# OBI_SlaveBoard_rev4.net
KiCad netlist of a schematic drawn in EAGLE
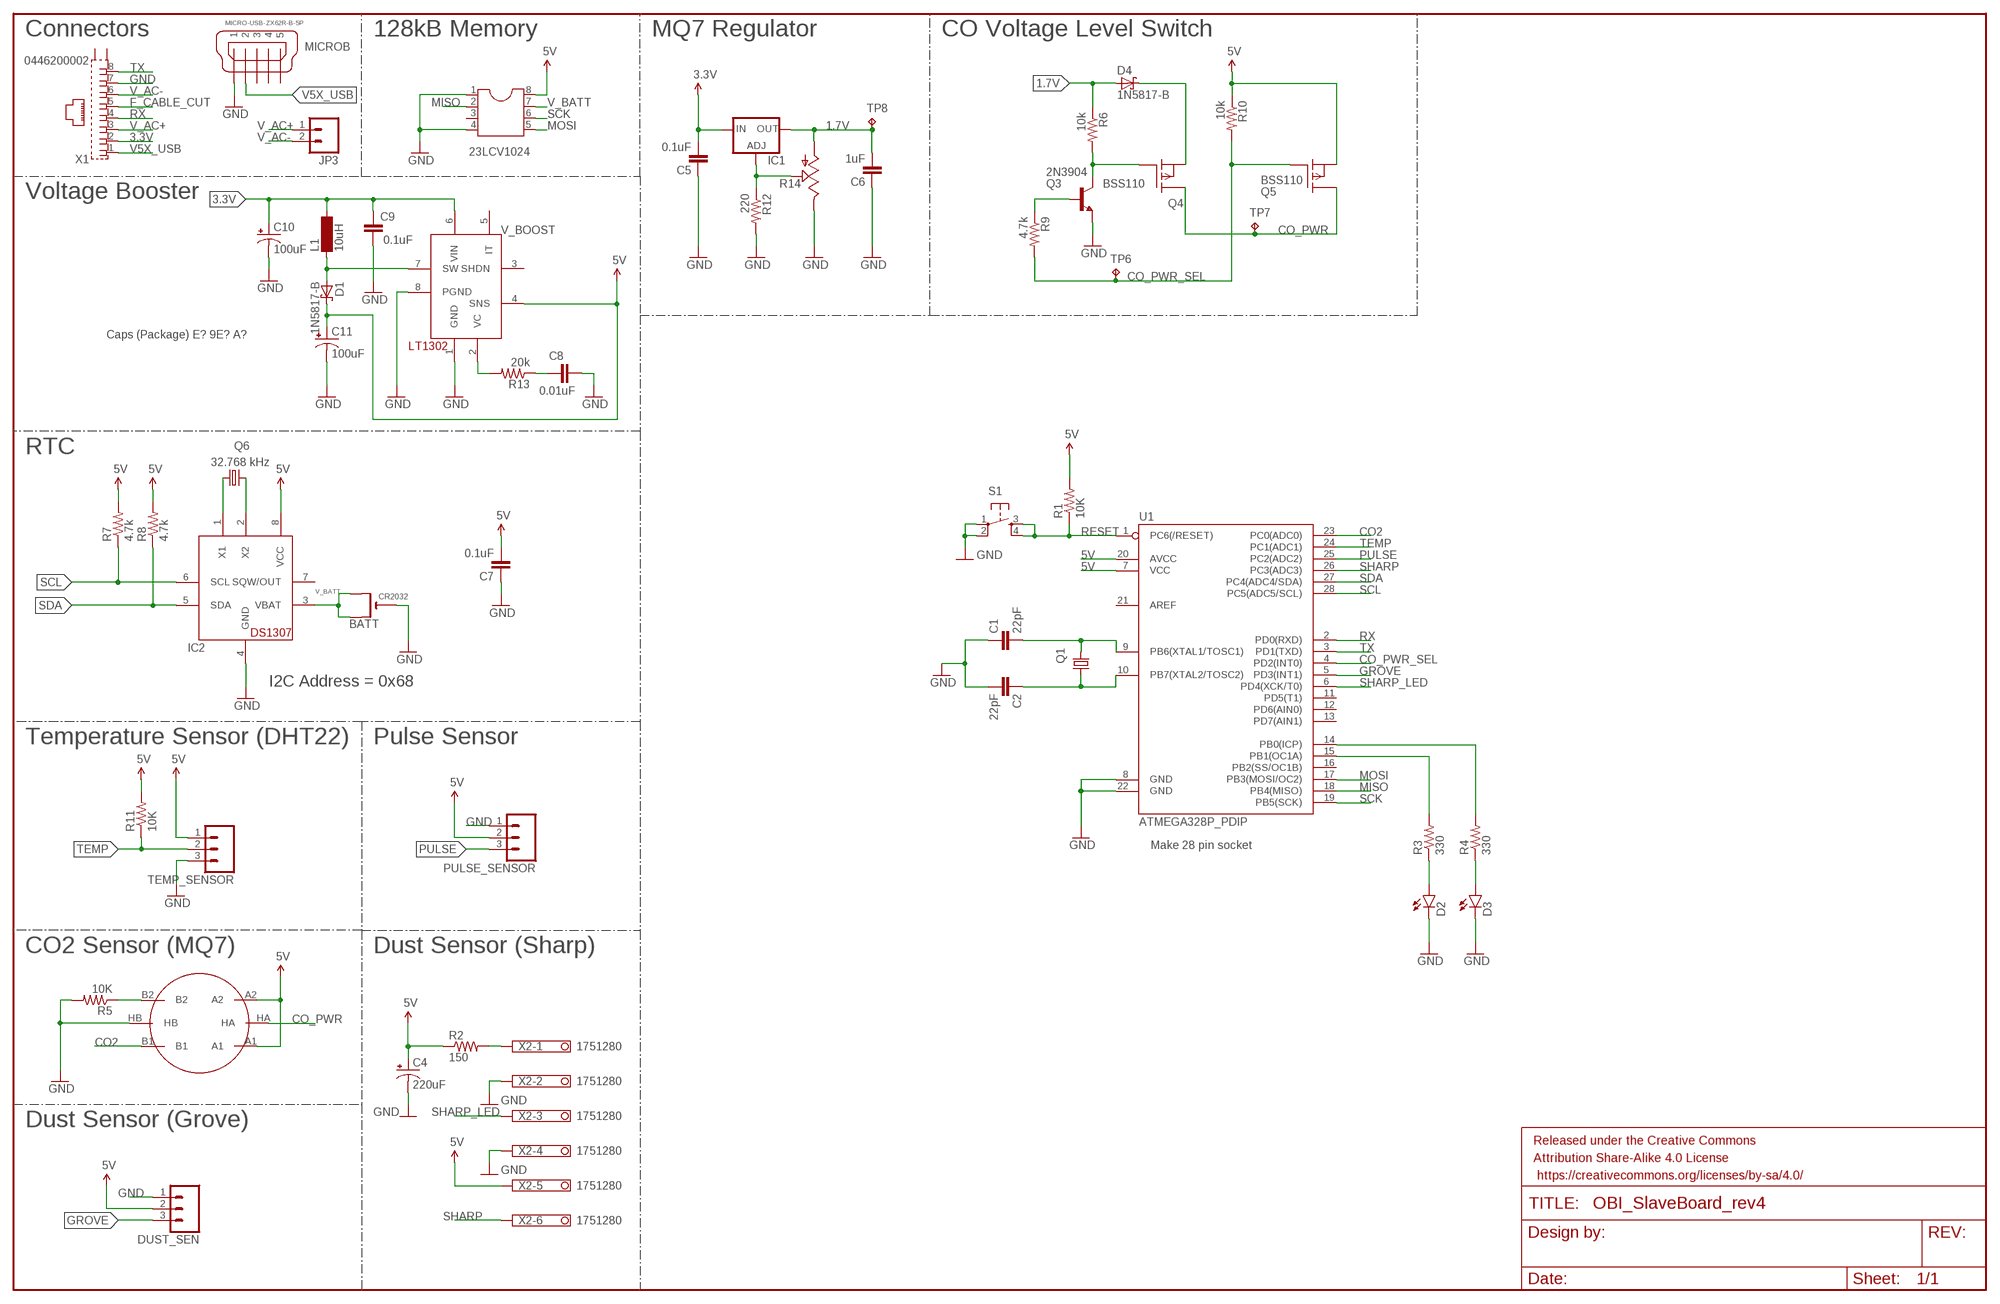
[diagram p0: schematic, sheet 1]

(export (version "E")
  (design (tool "Eeschema 10.0.6"))
  (components
    (comp (ref "23LCV1024")
      (value "DIL8S")
      (footprint "eagle-import:SOCKET-08")
      (libsource (lib "eagle-import") (part "DIL8S"))
    )
    (comp (ref "BATT")
      (value "CR2032THM")
      (footprint "eagle-import:CR2032-THRU")
      (libsource (lib "eagle-import") (part "CR2032THM"))
    )
    (comp (ref "C1")
      (value "22pF")
      (footprint "eagle-import:CAP-PTH-SMALL-KIT")
      (libsource (lib "eagle-import") (part "CAPKIT"))
    )
    (comp (ref "C2")
      (value "22pF")
      (footprint "eagle-import:CAP-PTH-SMALL-KIT")
      (libsource (lib "eagle-import") (part "CAPKIT"))
    )
    (comp (ref "C4")
      (value "220uF")
      (footprint "eagle-import:CPOL-RADIAL-10UF-25V")
      (libsource (lib "eagle-import") (part "CAP_POLPTH2"))
    )
    (comp (ref "C5")
      (value "0.1uF")
      (footprint "eagle-import:CAP-PTH-SMALL-KIT")
      (libsource (lib "eagle-import") (part "CAPKIT"))
    )
    (comp (ref "C6")
      (value "1uF")
      (footprint "eagle-import:CAP-PTH-SMALL-KIT")
      (libsource (lib "eagle-import") (part "CAPKIT"))
    )
    (comp (ref "C7")
      (value "0.1uF")
      (footprint "eagle-import:CAP-PTH-SMALL-KIT")
      (libsource (lib "eagle-import") (part "CAPKIT"))
    )
    (comp (ref "C8")
      (value "0.01uF")
      (footprint "eagle-import:CAP-PTH-SMALL-KIT")
      (libsource (lib "eagle-import") (part "CAPKIT"))
    )
    (comp (ref "C9")
      (value "0.1uF")
      (footprint "eagle-import:CAP-PTH-SMALL-KIT")
      (libsource (lib "eagle-import") (part "CAPKIT"))
    )
    (comp (ref "C10")
      (value "100uF")
      (footprint "eagle-import:TT2D5")
      (libsource (lib "eagle-import") (part "CPOL-USTT2D5"))
    )
    (comp (ref "C11")
      (value "100uF")
      (footprint "eagle-import:TT2D5")
      (libsource (lib "eagle-import") (part "CPOL-USTT2D5"))
    )
    (comp (ref "CO2_SENSOR")
      (value "METHANE_SENSOR")
      (footprint "eagle-import:MQ-3")
      (libsource (lib "eagle-import") (part "METHANE_SENSOR"))
    )
    (comp (ref "D1")
      (value "1N5817-B")
      (footprint "eagle-import:DO41-10")
      (libsource (lib "eagle-import") (part "SCHOTTKY-DIODEDO41"))
    )
    (comp (ref "D2")
      (value "LED5MM")
      (footprint "eagle-import:LED5MM")
      (libsource (lib "eagle-import") (part "LED5MM"))
    )
    (comp (ref "D3")
      (value "LED5MM")
      (footprint "eagle-import:LED5MM")
      (libsource (lib "eagle-import") (part "LED5MM"))
    )
    (comp (ref "D4")
      (value "1N5817-B")
      (footprint "eagle-import:DO41-10")
      (libsource (lib "eagle-import") (part "SCHOTTKY-DIODEDO41"))
    )
    (comp (ref "DUST_SEN")
      (value "M03SCREW")
      (footprint "eagle-import:SCREWTERMINAL-3.5MM-3")
      (libsource (lib "eagle-import") (part "M03SCREW"))
    )
    (comp (ref "FRAME1")
      (value "FRAME-LEDGER")
      (footprint "eagle-import:CREATIVE_COMMONS")
      (libsource (lib "eagle-import") (part "FRAME-LEDGER"))
    )
    (comp (ref "IC1")
      (value "LM317TS")
      (footprint "eagle-import:317TS")
      (libsource (lib "eagle-import") (part "LM317TS"))
    )
    (comp (ref "IC2")
      (value "DS1307")
      (footprint "eagle-import:DIL08")
      (libsource (lib "eagle-import") (part "DS1307"))
    )
    (comp (ref "JP3")
      (value "M023.5MM")
      (footprint "eagle-import:SCREWTERMINAL-3.5MM-2")
      (libsource (lib "eagle-import") (part "M023.5MM"))
    )
    (comp (ref "L1")
      (value "10uH")
      (footprint "eagle-import:BS11")
      (libsource (lib "eagle-import") (part "BS11"))
    )
    (comp (ref "MICROB")
      (value "MICRO-USB-ZX62R-B-5P")
      (footprint "eagle-import:ZX62R-B-5P")
      (libsource (lib "eagle-import") (part "MICRO-USB-ZX62R-B-5P"))
    )
    (comp (ref "PULSE_SENSOR")
      (value "M03SCREW")
      (footprint "eagle-import:SCREWTERMINAL-3.5MM-3")
      (libsource (lib "eagle-import") (part "M03SCREW"))
    )
    (comp (ref "Q1")
      (value "CRYSTALHC49S")
      (footprint "eagle-import:HC49_S")
      (libsource (lib "eagle-import") (part "CRYSTALHC49S"))
    )
    (comp (ref "Q3")
      (value "2N3904")
      (footprint "eagle-import:TO-92")
      (libsource (lib "eagle-import") (part "TRANSISTOR_NPN2N3904"))
    )
    (comp (ref "Q4")
      (value "BSS110")
      (footprint "eagle-import:TO92")
      (libsource (lib "eagle-import") (part "BSS110"))
    )
    (comp (ref "Q5")
      (value "BSS110")
      (footprint "eagle-import:TO92")
      (libsource (lib "eagle-import") (part "BSS110"))
    )
    (comp (ref "Q6")
      (value "32.768 kHz")
      (footprint "eagle-import:TC26V")
      (libsource (lib "eagle-import") (part "CRYSTALTC26V"))
    )
    (comp (ref "R1")
      (value "10K")
      (footprint "eagle-import:AXIAL-0.4")
      (libsource (lib "eagle-import") (part "RESISTORPTH-1/4W"))
    )
    (comp (ref "R2")
      (value "150")
      (footprint "eagle-import:AXIAL-0.4")
      (libsource (lib "eagle-import") (part "SparkFun-Resistors_RESISTORPTH-1/4W"))
    )
    (comp (ref "R3")
      (value "330")
      (footprint "eagle-import:AXIAL-0.4")
      (libsource (lib "eagle-import") (part "SparkFun-Resistors_RESISTORPTH-1/4W"))
    )
    (comp (ref "R4")
      (value "330")
      (footprint "eagle-import:AXIAL-0.4")
      (libsource (lib "eagle-import") (part "SparkFun-Resistors_RESISTORPTH-1/4W"))
    )
    (comp (ref "R5")
      (value "10K")
      (footprint "eagle-import:AXIAL-0.4")
      (libsource (lib "eagle-import") (part "RESISTORPTH-1/4W"))
    )
    (comp (ref "R6")
      (value "10k")
      (footprint "eagle-import:AXIAL-0.4")
      (libsource (lib "eagle-import") (part "SparkFun-Resistors_RESISTORPTH-1/4W"))
    )
    (comp (ref "R7")
      (value "4.7k")
      (footprint "eagle-import:AXIAL-0.4")
      (libsource (lib "eagle-import") (part "RESISTORPTH-1/4W"))
    )
    (comp (ref "R8")
      (value "4.7k")
      (footprint "eagle-import:AXIAL-0.4")
      (libsource (lib "eagle-import") (part "RESISTORPTH-1/4W"))
    )
    (comp (ref "R9")
      (value "4.7k")
      (footprint "eagle-import:AXIAL-0.4")
      (libsource (lib "eagle-import") (part "SparkFun-Resistors_RESISTORPTH-1/4W"))
    )
    (comp (ref "R10")
      (value "10k")
      (footprint "eagle-import:AXIAL-0.4")
      (libsource (lib "eagle-import") (part "SparkFun-Resistors_RESISTORPTH-1/4W"))
    )
    (comp (ref "R11")
      (value "10K")
      (footprint "eagle-import:AXIAL-0.4")
      (libsource (lib "eagle-import") (part "SparkFun-Resistors_RESISTORPTH-1/4W"))
    )
    (comp (ref "R12")
      (value "220")
      (footprint "eagle-import:AXIAL-0.4")
      (libsource (lib "eagle-import") (part "SparkFun-Resistors_RESISTORPTH-1/4W"))
    )
    (comp (ref "R13")
      (value "20k")
      (footprint "eagle-import:AXIAL-0.4")
      (libsource (lib "eagle-import") (part "SparkFun-Resistors_RESISTORPTH-1/4W"))
    )
    (comp (ref "R14")
      (value "TRIM_US-CT6")
      (footprint "eagle-import:CT6")
      (libsource (lib "eagle-import") (part "TRIM_US-CT6"))
    )
    (comp (ref "S1")
      (value "TAC_SWITCHPTH")
      (footprint "eagle-import:TACTILE-PTH")
      (libsource (lib "eagle-import") (part "TAC_SWITCHPTH"))
    )
    (comp (ref "TEMP_SENSOR")
      (value "M03SCREW")
      (footprint "eagle-import:SCREWTERMINAL-3.5MM-3")
      (libsource (lib "eagle-import") (part "M03SCREW"))
    )
    (comp (ref "TP6")
      (value "TPPAD1-13")
      (footprint "eagle-import:P1-13")
      (libsource (lib "eagle-import") (part "TPPAD1-13"))
    )
    (comp (ref "TP7")
      (value "TPPAD1-13")
      (footprint "eagle-import:P1-13")
      (libsource (lib "eagle-import") (part "TPPAD1-13"))
    )
    (comp (ref "TP8")
      (value "TPPAD1-13")
      (footprint "eagle-import:P1-13")
      (libsource (lib "eagle-import") (part "TPPAD1-13"))
    )
    (comp (ref "U1")
      (value "ATMEGA328P_PDIP")
      (footprint "eagle-import:DIL28-3")
      (libsource (lib "eagle-import") (part "ATMEGA328P_PDIP"))
    )
    (comp (ref "V_BOOST")
      (value "LT1302")
      (footprint "eagle-import:DIL08")
      (libsource (lib "eagle-import") (part "LT1302"))
    )
    (comp (ref "X1")
      (value "0446200002")
      (footprint "eagle-import:0446200002")
      (fields (field (name "MF") "MOLEX"))
      (libsource (lib "eagle-import") (part "0446200002"))
    )
    (comp (ref "X2")
      (value "1751280")
      (footprint "eagle-import:1751280")
      (libsource (lib "eagle-import") (part "1751280"))
    )
  )
  (nets
    (net (code "1") (name "/CO2") (class "Default")
      (node (ref "CO2_SENSOR") (pin "B1") (pinfunction "B1_B1") (pintype "bidirectional"))
      (node (ref "U1") (pin "23") (pinfunction "PC0(ADC0)_23") (pintype "bidirectional"))
    )
    (net (code "2") (name "/CO_PWR") (class "Default")
      (node (ref "CO2_SENSOR") (pin "HA") (pinfunction "HA_HA") (pintype "bidirectional"))
      (node (ref "Q4") (pin "3") (pinfunction "D_3") (pintype "passive"))
      (node (ref "Q5") (pin "3") (pinfunction "D_3") (pintype "passive"))
      (node (ref "TP7") (pin "TP") (pinfunction "TP_TP") (pintype "input"))
    )
    (net (code "3") (name "/CO_PWR_SEL") (class "Default")
      (node (ref "Q5") (pin "2") (pinfunction "G_2") (pintype "passive"))
      (node (ref "R10") (pin "P$2") (pinfunction "2_P$2") (pintype "passive"))
      (node (ref "R9") (pin "P$2") (pinfunction "2_P$2") (pintype "passive"))
      (node (ref "TP6") (pin "TP") (pinfunction "TP_TP") (pintype "input"))
      (node (ref "U1") (pin "4") (pinfunction "PD2(INT0)_4") (pintype "bidirectional"))
    )
    (net (code "4") (name "/F_CABLE_CUT") (class "Default")
      (node (ref "X1") (pin "5") (pinfunction "5_5") (pintype "passive"))
    )
    (net (code "5") (name "/MISO") (class "Default")
      (node (ref "23LCV1024") (pin "2") (pinfunction "2_2") (pintype "passive"))
      (node (ref "U1") (pin "18") (pinfunction "PB4(MISO)_18") (pintype "bidirectional"))
    )
    (net (code "6") (name "/MOSI") (class "Default")
      (node (ref "23LCV1024") (pin "5") (pinfunction "5_5") (pintype "passive"))
      (node (ref "U1") (pin "17") (pinfunction "PB3(MOSI/OC2)_17") (pintype "bidirectional"))
    )
    (net (code "7") (name "/RESET") (class "Default")
      (node (ref "R1") (pin "P$1") (pinfunction "1_P$1") (pintype "passive"))
      (node (ref "S1") (pin "3") (pinfunction "3_3") (pintype "passive"))
      (node (ref "S1") (pin "4") (pinfunction "4_4") (pintype "passive"))
      (node (ref "U1") (pin "1") (pinfunction "PC6(/RESET)_1") (pintype "bidirectional"))
    )
    (net (code "8") (name "/RX") (class "Default")
      (node (ref "U1") (pin "2") (pinfunction "PD0(RXD)_2") (pintype "bidirectional"))
      (node (ref "X1") (pin "4") (pinfunction "4_4") (pintype "passive"))
    )
    (net (code "9") (name "/SCK") (class "Default")
      (node (ref "23LCV1024") (pin "6") (pinfunction "6_6") (pintype "passive"))
      (node (ref "U1") (pin "19") (pinfunction "PB5(SCK)_19") (pintype "bidirectional"))
    )
    (net (code "10") (name "/SHARP") (class "Default")
      (node (ref "U1") (pin "26") (pinfunction "PC3(ADC3)_26") (pintype "bidirectional"))
      (node (ref "X2") (pin "6") (pinfunction "K_6") (pintype "passive"))
    )
    (net (code "11") (name "/SHARP_LED") (class "Default")
      (node (ref "U1") (pin "6") (pinfunction "PD4(XCK/T0)_6") (pintype "bidirectional"))
      (node (ref "X2") (pin "3") (pinfunction "K_3") (pintype "passive"))
    )
    (net (code "12") (name "/TX") (class "Default")
      (node (ref "U1") (pin "3") (pinfunction "PD1(TXD)_3") (pintype "bidirectional"))
      (node (ref "X1") (pin "8") (pinfunction "8_8") (pintype "passive"))
    )
    (net (code "13") (name "/V_AC+") (class "Default")
      (node (ref "JP3") (pin "1") (pinfunction "1_1") (pintype "passive"))
      (node (ref "X1") (pin "3") (pinfunction "3_3") (pintype "passive"))
    )
    (net (code "14") (name "/V_AC-") (class "Default")
      (node (ref "JP3") (pin "2") (pinfunction "2_2") (pintype "passive"))
      (node (ref "X1") (pin "6") (pinfunction "6_6") (pintype "passive"))
    )
    (net (code "15") (name "/V_BATT") (class "Default")
      (node (ref "23LCV1024") (pin "7") (pinfunction "7_7") (pintype "passive"))
      (node (ref "BATT") (pin "+1") (pinfunction "+_+1") (pintype "passive"))
      (node (ref "BATT") (pin "+2") (pinfunction "+1_+2") (pintype "passive"))
      (node (ref "IC2") (pin "3") (pinfunction "VBAT_3") (pintype "power_in"))
    )
    (net (code "16") (name "1.7V") (class "Default")
      (node (ref "C6") (pin "2") (pinfunction "2_2") (pintype "passive"))
      (node (ref "D4") (pin "A") (pinfunction "A_A") (pintype "passive"))
      (node (ref "IC1") (pin "2") (pinfunction "OUT_2") (pintype "passive"))
      (node (ref "R14") (pin "A") (pinfunction "A_A") (pintype "passive"))
      (node (ref "R6") (pin "P$1") (pinfunction "1_P$1") (pintype "passive"))
      (node (ref "TP8") (pin "TP") (pinfunction "TP_TP") (pintype "input"))
    )
    (net (code "17") (name "3.3V") (class "Default")
      (node (ref "C10") (pin "+") (pinfunction "+_+") (pintype "passive"))
      (node (ref "C5") (pin "2") (pinfunction "2_2") (pintype "passive"))
      (node (ref "C9") (pin "1") (pinfunction "1_1") (pintype "passive"))
      (node (ref "IC1") (pin "3") (pinfunction "IN_3") (pintype "input"))
      (node (ref "L1") (pin "2") (pinfunction "2_2") (pintype "passive"))
      (node (ref "V_BOOST") (pin "6") (pinfunction "VIN_6") (pintype "input"))
      (node (ref "X1") (pin "2") (pinfunction "2_2") (pintype "passive"))
    )
    (net (code "18") (name "5V") (class "Default")
      (node (ref "23LCV1024") (pin "8") (pinfunction "8_8") (pintype "passive"))
      (node (ref "C11") (pin "+") (pinfunction "+_+") (pintype "passive"))
      (node (ref "C4") (pin "1") (pinfunction "+_1") (pintype "passive"))
      (node (ref "C7") (pin "2") (pinfunction "2_2") (pintype "passive"))
      (node (ref "CO2_SENSOR") (pin "A1") (pinfunction "A1_A1") (pintype "bidirectional"))
      (node (ref "CO2_SENSOR") (pin "A2") (pinfunction "A2_A2") (pintype "bidirectional"))
      (node (ref "D1") (pin "C") (pinfunction "C_C") (pintype "passive"))
      (node (ref "DUST_SEN") (pin "2") (pinfunction "2_2") (pintype "passive"))
      (node (ref "IC2") (pin "8") (pinfunction "VCC_8") (pintype "power_in"))
      (node (ref "PULSE_SENSOR") (pin "2") (pinfunction "2_2") (pintype "passive"))
      (node (ref "Q5") (pin "1") (pinfunction "S_1") (pintype "passive"))
      (node (ref "R1") (pin "P$2") (pinfunction "2_P$2") (pintype "passive"))
      (node (ref "R10") (pin "P$1") (pinfunction "1_P$1") (pintype "passive"))
      (node (ref "R11") (pin "P$2") (pinfunction "2_P$2") (pintype "passive"))
      (node (ref "R2") (pin "P$1") (pinfunction "1_P$1") (pintype "passive"))
      (node (ref "R7") (pin "P$2") (pinfunction "2_P$2") (pintype "passive"))
      (node (ref "R8") (pin "P$2") (pinfunction "2_P$2") (pintype "passive"))
      (node (ref "TEMP_SENSOR") (pin "1") (pinfunction "1_1") (pintype "passive"))
      (node (ref "U1") (pin "20") (pinfunction "AVCC_20") (pintype "bidirectional"))
      (node (ref "U1") (pin "7") (pinfunction "VCC_7") (pintype "bidirectional"))
      (node (ref "V_BOOST") (pin "4") (pinfunction "SNS_4") (pintype "passive"))
      (node (ref "X2") (pin "5") (pinfunction "K_5") (pintype "passive"))
    )
    (net (code "19") (name "GND") (class "Default")
      (node (ref "23LCV1024") (pin "1") (pinfunction "1_1") (pintype "passive"))
      (node (ref "23LCV1024") (pin "4") (pinfunction "4_4") (pintype "passive"))
      (node (ref "BATT") (pin "-") (pinfunction "-_-") (pintype "passive"))
      (node (ref "C1") (pin "1") (pinfunction "1_1") (pintype "passive"))
      (node (ref "C10") (pin "-") (pinfunction "-_-") (pintype "passive"))
      (node (ref "C11") (pin "-") (pinfunction "-_-") (pintype "passive"))
      (node (ref "C2") (pin "2") (pinfunction "2_2") (pintype "passive"))
      (node (ref "C4") (pin "2") (pinfunction "-_2") (pintype "passive"))
      (node (ref "C5") (pin "1") (pinfunction "1_1") (pintype "passive"))
      (node (ref "C6") (pin "1") (pinfunction "1_1") (pintype "passive"))
      (node (ref "C7") (pin "1") (pinfunction "1_1") (pintype "passive"))
      (node (ref "C8") (pin "1") (pinfunction "1_1") (pintype "passive"))
      (node (ref "C9") (pin "2") (pinfunction "2_2") (pintype "passive"))
      (node (ref "CO2_SENSOR") (pin "HB") (pinfunction "HB_HB") (pintype "bidirectional"))
      (node (ref "D2") (pin "K") (pinfunction "C_K") (pintype "passive"))
      (node (ref "D3") (pin "K") (pinfunction "C_K") (pintype "passive"))
      (node (ref "DUST_SEN") (pin "1") (pinfunction "1_1") (pintype "passive"))
      (node (ref "IC2") (pin "4") (pinfunction "GND_4") (pintype "power_in"))
      (node (ref "MICROB") (pin "1") (pinfunction "1_1") (pintype "input"))
      (node (ref "PULSE_SENSOR") (pin "1") (pinfunction "1_1") (pintype "passive"))
      (node (ref "Q3") (pin "1") (pinfunction "E_1") (pintype "passive"))
      (node (ref "R12") (pin "P$2") (pinfunction "2_P$2") (pintype "passive"))
      (node (ref "R14") (pin "E") (pinfunction "E_E") (pintype "passive"))
      (node (ref "R5") (pin "P$2") (pinfunction "2_P$2") (pintype "passive"))
      (node (ref "S1") (pin "1") (pinfunction "1_1") (pintype "passive"))
      (node (ref "S1") (pin "2") (pinfunction "2_2") (pintype "passive"))
      (node (ref "TEMP_SENSOR") (pin "3") (pinfunction "3_3") (pintype "passive"))
      (node (ref "U1") (pin "22") (pinfunction "GND_22") (pintype "bidirectional"))
      (node (ref "U1") (pin "8") (pinfunction "GND_8") (pintype "bidirectional"))
      (node (ref "V_BOOST") (pin "1") (pinfunction "GND_1") (pintype "input"))
      (node (ref "V_BOOST") (pin "8") (pinfunction "PGND_8") (pintype "input"))
      (node (ref "X1") (pin "7") (pinfunction "7_7") (pintype "passive"))
      (node (ref "X2") (pin "2") (pinfunction "K_2") (pintype "passive"))
      (node (ref "X2") (pin "4") (pinfunction "K_4") (pintype "passive"))
    )
    (net (code "20") (name "GROVE") (class "Default")
      (node (ref "DUST_SEN") (pin "3") (pinfunction "3_3") (pintype "passive"))
      (node (ref "U1") (pin "5") (pinfunction "PD3(INT1)_5") (pintype "bidirectional"))
    )
    (net (code "21") (name "Net-(IC1-ADJ)") (class "Default")
      (node (ref "IC1") (pin "1") (pinfunction "ADJ_1") (pintype "input"))
      (node (ref "R12") (pin "P$1") (pinfunction "1_P$1") (pintype "passive"))
      (node (ref "R14") (pin "S") (pinfunction "S_S") (pintype "passive"))
    )
    (net (code "22") (name "Net-(IC2-X1)") (class "Default")
      (node (ref "IC2") (pin "1") (pinfunction "X1_1") (pintype "passive"))
      (node (ref "Q6") (pin "1") (pinfunction "1_1") (pintype "passive"))
    )
    (net (code "23") (name "Net-(IC2-X2)") (class "Default")
      (node (ref "IC2") (pin "2") (pinfunction "X2_2") (pintype "passive"))
      (node (ref "Q6") (pin "2") (pinfunction "2_2") (pintype "passive"))
    )
    (net (code "24") (name "Net-(Q3-B)") (class "Default")
      (node (ref "Q3") (pin "2") (pinfunction "B_2") (pintype "passive"))
      (node (ref "R9") (pin "P$1") (pinfunction "1_P$1") (pintype "passive"))
    )
    (net (code "25") (name "Net-(Q3-C)") (class "Default")
      (node (ref "Q3") (pin "3") (pinfunction "C_3") (pintype "passive"))
      (node (ref "Q4") (pin "2") (pinfunction "G_2") (pintype "passive"))
      (node (ref "R6") (pin "P$2") (pinfunction "2_P$2") (pintype "passive"))
    )
    (net (code "26") (name "Net-(Q4-S)") (class "Default")
      (node (ref "D4") (pin "C") (pinfunction "C_C") (pintype "passive"))
      (node (ref "Q4") (pin "1") (pinfunction "S_1") (pintype "passive"))
    )
    (net (code "27") (name "Net-(R2-2)") (class "Default")
      (node (ref "R2") (pin "P$2") (pinfunction "2_P$2") (pintype "passive"))
      (node (ref "X2") (pin "1") (pinfunction "K_1") (pintype "passive"))
    )
    (net (code "28") (name "Net-(R3-1)") (class "Default")
      (node (ref "D2") (pin "A") (pinfunction "A_A") (pintype "passive"))
      (node (ref "R3") (pin "P$1") (pinfunction "1_P$1") (pintype "passive"))
    )
    (net (code "29") (name "Net-(R3-2)") (class "Default")
      (node (ref "R3") (pin "P$2") (pinfunction "2_P$2") (pintype "passive"))
      (node (ref "U1") (pin "15") (pinfunction "PB1(OC1A)_15") (pintype "bidirectional"))
    )
    (net (code "30") (name "Net-(R4-1)") (class "Default")
      (node (ref "D3") (pin "A") (pinfunction "A_A") (pintype "passive"))
      (node (ref "R4") (pin "P$1") (pinfunction "1_P$1") (pintype "passive"))
    )
    (net (code "31") (name "Net-(R4-2)") (class "Default")
      (node (ref "R4") (pin "P$2") (pinfunction "2_P$2") (pintype "passive"))
      (node (ref "U1") (pin "14") (pinfunction "PB0(ICP)_14") (pintype "bidirectional"))
    )
    (net (code "32") (name "Net-(R5-1)") (class "Default")
      (node (ref "CO2_SENSOR") (pin "B2") (pinfunction "B2_B2") (pintype "bidirectional"))
      (node (ref "R5") (pin "P$1") (pinfunction "1_P$1") (pintype "passive"))
    )
    (net (code "33") (name "Net-(R13-1)") (class "Default")
      (node (ref "C8") (pin "2") (pinfunction "2_2") (pintype "passive"))
      (node (ref "R13") (pin "P$1") (pinfunction "1_P$1") (pintype "passive"))
    )
    (net (code "34") (name "Net-(R13-2)") (class "Default")
      (node (ref "R13") (pin "P$2") (pinfunction "2_P$2") (pintype "passive"))
      (node (ref "V_BOOST") (pin "2") (pinfunction "VC_2") (pintype "passive"))
    )
    (net (code "35") (name "Net-(U1-PB6(XTAL1{slash}TOSC1))") (class "Default")
      (node (ref "C1") (pin "2") (pinfunction "2_2") (pintype "passive"))
      (node (ref "Q1") (pin "2") (pinfunction "2_2") (pintype "passive"))
      (node (ref "U1") (pin "9") (pinfunction "PB6(XTAL1/TOSC1)_9") (pintype "bidirectional"))
    )
    (net (code "36") (name "Net-(U1-PB7(XTAL2{slash}TOSC2))") (class "Default")
      (node (ref "C2") (pin "1") (pinfunction "1_1") (pintype "passive"))
      (node (ref "Q1") (pin "1") (pinfunction "1_1") (pintype "passive"))
      (node (ref "U1") (pin "10") (pinfunction "PB7(XTAL2/TOSC2)_10") (pintype "bidirectional"))
    )
    (net (code "37") (name "Net-(V_BOOST-SW)") (class "Default")
      (node (ref "D1") (pin "A") (pinfunction "A_A") (pintype "passive"))
      (node (ref "L1") (pin "1") (pinfunction "1_1") (pintype "passive"))
      (node (ref "V_BOOST") (pin "7") (pinfunction "SW_7") (pintype "input"))
    )
    (net (code "38") (name "PULSE") (class "Default")
      (node (ref "PULSE_SENSOR") (pin "3") (pinfunction "3_3") (pintype "passive"))
      (node (ref "U1") (pin "25") (pinfunction "PC2(ADC2)_25") (pintype "bidirectional"))
    )
    (net (code "39") (name "SCL") (class "Default")
      (node (ref "IC2") (pin "6") (pinfunction "SCL_6") (pintype "bidirectional"))
      (node (ref "R7") (pin "P$1") (pinfunction "1_P$1") (pintype "passive"))
      (node (ref "U1") (pin "28") (pinfunction "PC5(ADC5/SCL)_28") (pintype "bidirectional"))
    )
    (net (code "40") (name "SDA") (class "Default")
      (node (ref "IC2") (pin "5") (pinfunction "SDA_5") (pintype "bidirectional"))
      (node (ref "R8") (pin "P$1") (pinfunction "1_P$1") (pintype "passive"))
      (node (ref "U1") (pin "27") (pinfunction "PC4(ADC4/SDA)_27") (pintype "bidirectional"))
    )
    (net (code "41") (name "TEMP") (class "Default")
      (node (ref "R11") (pin "P$1") (pinfunction "1_P$1") (pintype "passive"))
      (node (ref "TEMP_SENSOR") (pin "2") (pinfunction "2_2") (pintype "passive"))
      (node (ref "U1") (pin "24") (pinfunction "PC1(ADC1)_24") (pintype "bidirectional"))
    )
    (net (code "42") (name "V5X_USB") (class "Default")
      (node (ref "MICROB") (pin "2") (pinfunction "2_2") (pintype "input"))
      (node (ref "X1") (pin "1") (pinfunction "1_1") (pintype "passive"))
    )
    (net (code "43") (name "unconnected-(23LCV1024-Pad3)") (class "Default")
      (node (ref "23LCV1024") (pin "3") (pinfunction "3_3") (pintype "passive"))
    )
    (net (code "44") (name "unconnected-(IC2-SQW{slash}OUT-Pad7)") (class "Default")
      (node (ref "IC2") (pin "7") (pinfunction "SQW/OUT_7") (pintype "bidirectional"))
    )
    (net (code "45") (name "unconnected-(MICROB-Pad3)") (class "Default")
      (node (ref "MICROB") (pin "3") (pinfunction "3_3") (pintype "input"))
    )
    (net (code "46") (name "unconnected-(MICROB-Pad4)") (class "Default")
      (node (ref "MICROB") (pin "4") (pinfunction "4_4") (pintype "input"))
    )
    (net (code "47") (name "unconnected-(MICROB-Pad5)") (class "Default")
      (node (ref "MICROB") (pin "5") (pinfunction "5_5") (pintype "input"))
    )
    (net (code "48") (name "unconnected-(U1-AREF-Pad21)") (class "Default")
      (node (ref "U1") (pin "21") (pinfunction "AREF_21") (pintype "bidirectional"))
    )
    (net (code "49") (name "unconnected-(U1-PB2(SS{slash}OC1B)-Pad16)") (class "Default")
      (node (ref "U1") (pin "16") (pinfunction "PB2(SS/OC1B)_16") (pintype "bidirectional"))
    )
    (net (code "50") (name "unconnected-(U1-PD5(T1)-Pad11)") (class "Default")
      (node (ref "U1") (pin "11") (pinfunction "PD5(T1)_11") (pintype "bidirectional"))
    )
    (net (code "51") (name "unconnected-(U1-PD6(AIN0)-Pad12)") (class "Default")
      (node (ref "U1") (pin "12") (pinfunction "PD6(AIN0)_12") (pintype "bidirectional"))
    )
    (net (code "52") (name "unconnected-(U1-PD7(AIN1)-Pad13)") (class "Default")
      (node (ref "U1") (pin "13") (pinfunction "PD7(AIN1)_13") (pintype "bidirectional"))
    )
    (net (code "53") (name "unconnected-(V_BOOST-IT-Pad5)") (class "Default")
      (node (ref "V_BOOST") (pin "5") (pinfunction "IT_5") (pintype "input"))
    )
    (net (code "54") (name "unconnected-(V_BOOST-SHDN-Pad3)") (class "Default")
      (node (ref "V_BOOST") (pin "3") (pinfunction "SHDN_3") (pintype "input"))
    )
    (net (code "55") (name "unconnected-(X1-S1-PadS@1)") (class "Default")
      (node (ref "X1") (pin "S@1") (pinfunction "S1_S@1") (pintype "passive"))
    )
    (net (code "56") (name "unconnected-(X1-S2-PadS@2)") (class "Default")
      (node (ref "X1") (pin "S@2") (pinfunction "S2_S@2") (pintype "passive"))
    )
  )
)
